# FV-1.net
KiCad netlist of a schematic drawn in Altium Designer
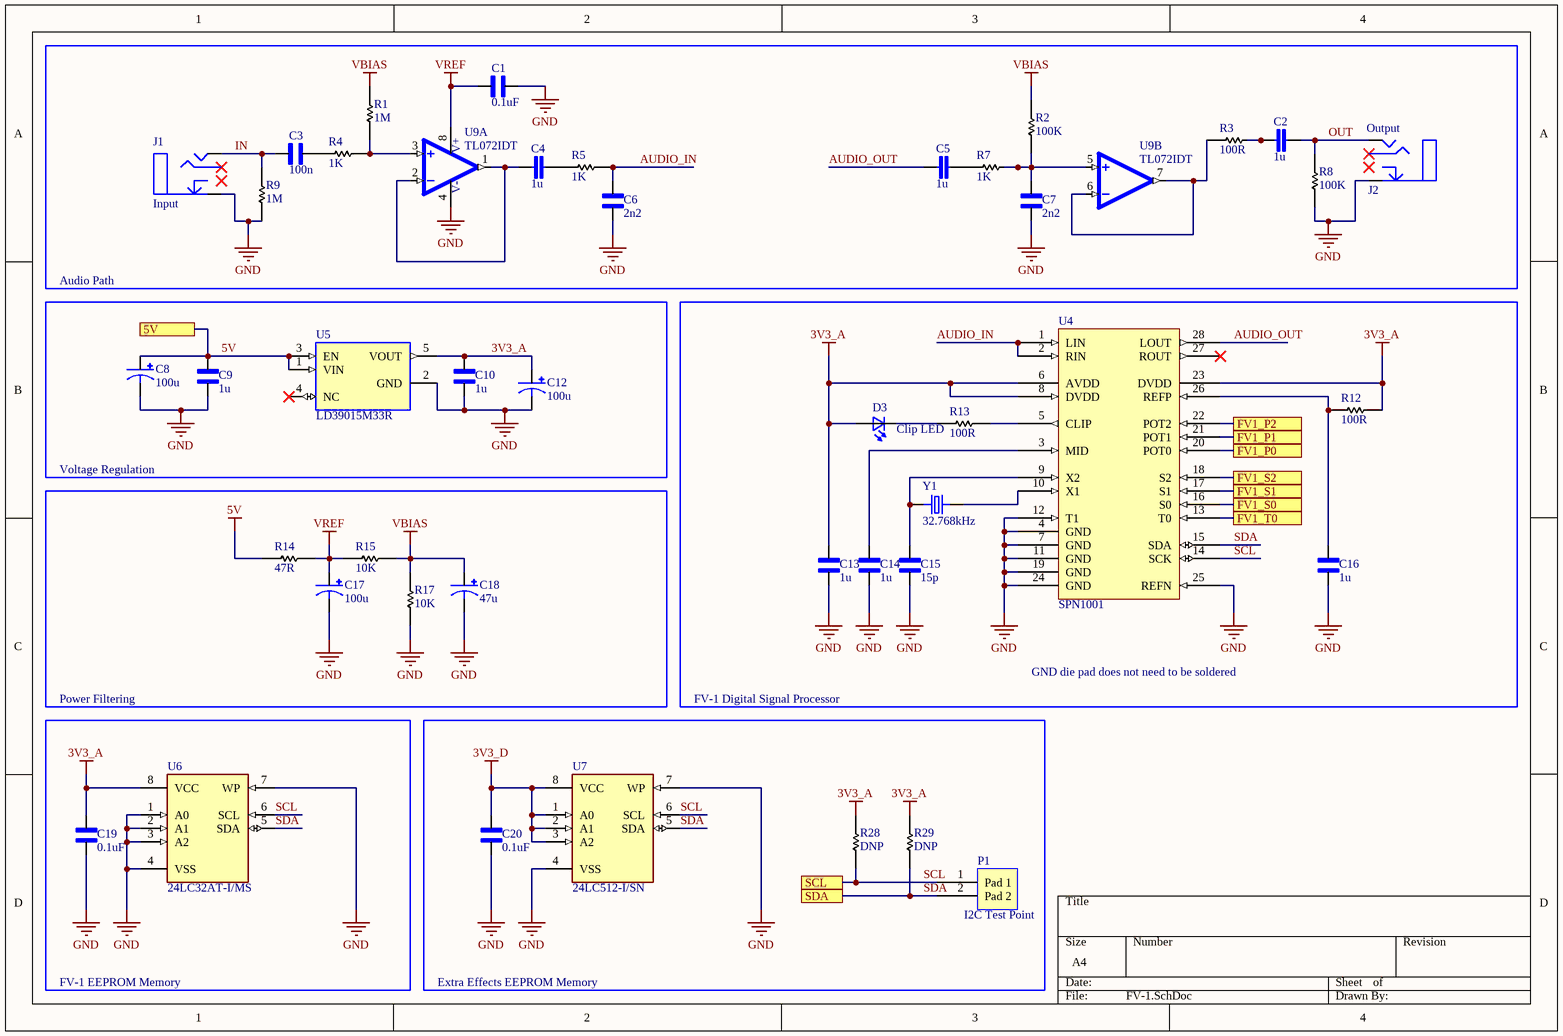
[diagram p0: FV-1.SchDoc]

(export (version "E")
  (design (tool "Eeschema 10.0.6"))
  (components
    (comp (ref "C1")
      (value "0.1uF")
      (footprint "CHIP_0603")
      (description "Generic 0603 Ceramic Capacitor")
      (fields (field (name "MP") "AC0402FR-071ML") (field (name "MF") "Yageo"))
      (libsource (lib "") (part "0603 Ceramic Capacitor_1"))
    )
    (comp (ref "C2")
      (value "1u")
      (footprint "CHIP_1210")
      (description "CAP FILM 1UF 16V 20%")
      (fields
        (field (name "MANUFACTURER") "Panasonic")
        (field (name "MANUFACTURER PART NUMBER") "ECP-U1C105MA5")
      )
      (libsource (lib "Guitar_Multi_Effect_lib") (part "ECP-U1C105MA5"))
    )
    (comp (ref "C3")
      (value "100n")
      (footprint "CAPC3216X180N")
      (description "50V 100nF C0G ±5% 1206 Multilayer Ceramic Capacitors")
      (libsource (lib "Guitar_Multi_Effect_lib") (part "GRM31C5C1H104JA01L"))
    )
    (comp (ref "C4")
      (value "1u")
      (footprint "CHIP_1210")
      (description "CAP FILM 1UF 16V 20%")
      (fields
        (field (name "MANUFACTURER") "Panasonic")
        (field (name "MANUFACTURER PART NUMBER") "ECP-U1C105MA5")
      )
      (libsource (lib "Guitar_Multi_Effect_lib") (part "ECP-U1C105MA5"))
    )
    (comp (ref "C5")
      (value "1u")
      (footprint "CHIP_1210")
      (description "CAP FILM 1UF 16V 20%")
      (fields
        (field (name "MANUFACTURER") "Panasonic")
        (field (name "MANUFACTURER PART NUMBER") "ECP-U1C105MA5")
      )
      (libsource (lib "Guitar_Multi_Effect_lib") (part "ECP-U1C105MA5"))
    )
    (comp (ref "C6")
      (value "2n2")
      (footprint "CHIP_0603")
      (description "2200PF 50V C0G/NP0 0603")
      (libsource (lib "Guitar_Multi_Effect_lib") (part "GRM1885C1H222JA01D"))
    )
    (comp (ref "C7")
      (value "2n2")
      (footprint "CHIP_0603")
      (description "2200PF 50V C0G/NP0 0603")
      (libsource (lib "Guitar_Multi_Effect_lib") (part "GRM1885C1H222JA01D"))
    )
    (comp (ref "C8")
      (value "100u")
      (footprint "UCD1E101MCL1GS")
      (description "CAP ALUM 100UF 25V SMD")
      (libsource (lib "Guitar_Multi_Effect_lib") (part "UCD1E101MCL1GS"))
    )
    (comp (ref "C9")
      (value "1u")
      (footprint "CHIP_0603")
      (description "Generic 0603 Ceramic Capacitor")
      (fields (field (name "MP") "AC0402FR-071ML") (field (name "MF") "Yageo"))
      (libsource (lib "Guitar_Multi_Effect_lib") (part "0603 Ceramic Capacitor"))
    )
    (comp (ref "C10")
      (value "1u")
      (footprint "CHIP_0603")
      (description "Generic 0603 Ceramic Capacitor")
      (fields (field (name "MP") "AC0402FR-071ML") (field (name "MF") "Yageo"))
      (libsource (lib "Guitar_Multi_Effect_lib") (part "0603 Ceramic Capacitor"))
    )
    (comp (ref "C12")
      (value "100u")
      (footprint "UCD1E101MCL1GS")
      (description "CAP ALUM 100UF 25V SMD")
      (libsource (lib "Guitar_Multi_Effect_lib") (part "UCD1E101MCL1GS"))
    )
    (comp (ref "C13")
      (value "1u")
      (footprint "CHIP_0603")
      (description "Generic 0603 Ceramic Capacitor")
      (fields (field (name "MP") "AC0402FR-071ML") (field (name "MF") "Yageo"))
      (libsource (lib "Guitar_Multi_Effect_lib") (part "0603 Ceramic Capacitor"))
    )
    (comp (ref "C14")
      (value "1u")
      (footprint "CHIP_0603")
      (description "Generic 0603 Ceramic Capacitor")
      (fields (field (name "MP") "AC0402FR-071ML") (field (name "MF") "Yageo"))
      (libsource (lib "Guitar_Multi_Effect_lib") (part "0603 Ceramic Capacitor"))
    )
    (comp (ref "C15")
      (value "15p")
      (footprint "CHIP_0603")
      (description "Generic 0603 Ceramic Capacitor")
      (fields (field (name "MP") "AC0402FR-071ML") (field (name "MF") "Yageo"))
      (libsource (lib "Guitar_Multi_Effect_lib") (part "0603 Ceramic Capacitor"))
    )
    (comp (ref "C16")
      (value "1u")
      (footprint "CHIP_0603")
      (description "Generic 0603 Ceramic Capacitor")
      (fields (field (name "MP") "AC0402FR-071ML") (field (name "MF") "Yageo"))
      (libsource (lib "Guitar_Multi_Effect_lib") (part "0603 Ceramic Capacitor"))
    )
    (comp (ref "C17")
      (value "100u")
      (footprint "UCD1E101MCL1GS")
      (description "CAP ALUM 100UF 25V SMD")
      (libsource (lib "Guitar_Multi_Effect_lib") (part "UCD1E101MCL1GS"))
    )
    (comp (ref "C18")
      (value "47u")
      (footprint "EEE1EA470WAP")
      (description "CAP ALUM 47UF 25V SMD")
      (libsource (lib "Guitar_Multi_Effect_lib") (part "EEE1EA470WAP"))
    )
    (comp (ref "C19")
      (value "0.1uF")
      (footprint "CHIP_0603")
      (description "Generic 0603 Ceramic Capacitor")
      (fields (field (name "MP") "AC0402FR-071ML") (field (name "MF") "Yageo"))
      (libsource (lib "Guitar_Multi_Effect_lib") (part "0603 Ceramic Capacitor"))
    )
    (comp (ref "C20")
      (value "0.1uF")
      (footprint "CHIP_0603")
      (description "Generic 0603 Ceramic Capacitor")
      (fields (field (name "MP") "AC0402FR-071ML") (field (name "MF") "Yageo"))
      (libsource (lib "Guitar_Multi_Effect_lib") (part "0603 Ceramic Capacitor"))
    )
    (comp (ref "D3")
      (value "Clip LED")
      (footprint "0603 LED Generic")
      (description "0603 Generic LED")
      (libsource (lib "Guitar_Multi_Effect_lib") (part "0603 Generic LED"))
    )
    (comp (ref "J1")
      (value "Input")
      (footprint "2 Test Points")
      (description "Sodler pads for audio jacks")
      (libsource (lib "Guitar_Multi_Effect_lib") (part "Audio_Solder_Pads"))
    )
    (comp (ref "J2")
      (value "Output")
      (footprint "2 Test Points")
      (description "Sodler pads for audio jacks")
      (libsource (lib "Guitar_Multi_Effect_lib") (part "Audio_Solder_Pads"))
    )
    (comp (ref "P1")
      (value "I2C Test Point")
      (footprint "2 Test Points")
      (libsource (lib "Guitar_Multi_Effect_lib") (part "Double Test Point"))
    )
    (comp (ref "R1")
      (value "1M")
      (footprint "CHIP_R_0603")
      (description "Generic 0603 Resistor")
      (libsource (lib "Guitar_Multi_Effect_lib") (part "0603 Generic Resistor"))
    )
    (comp (ref "R2")
      (value "100K")
      (footprint "CHIP_R_0603")
      (description "Generic 0603 Resistor")
      (libsource (lib "Guitar_Multi_Effect_lib") (part "0603 Generic Resistor"))
    )
    (comp (ref "R3")
      (value "100R")
      (footprint "CHIP_R_0603")
      (description "Generic 0603 Resistor")
      (libsource (lib "Guitar_Multi_Effect_lib") (part "0603 Generic Resistor"))
    )
    (comp (ref "R4")
      (value "1K")
      (footprint "CHIP_R_0603")
      (description "Generic 0603 Resistor")
      (libsource (lib "Guitar_Multi_Effect_lib") (part "0603 Generic Resistor"))
    )
    (comp (ref "R5")
      (value "1K")
      (footprint "CHIP_R_0603")
      (description "Generic 0603 Resistor")
      (libsource (lib "Guitar_Multi_Effect_lib") (part "0603 Generic Resistor"))
    )
    (comp (ref "R7")
      (value "1K")
      (footprint "CHIP_R_0603")
      (description "Generic 0603 Resistor")
      (libsource (lib "Guitar_Multi_Effect_lib") (part "0603 Generic Resistor"))
    )
    (comp (ref "R8")
      (value "100K")
      (footprint "CHIP_R_0603")
      (description "Generic 0603 Resistor")
      (libsource (lib "Guitar_Multi_Effect_lib") (part "0603 Generic Resistor"))
    )
    (comp (ref "R9")
      (value "1M")
      (footprint "CHIP_R_0603")
      (description "Generic 0603 Resistor")
      (libsource (lib "Guitar_Multi_Effect_lib") (part "0603 Generic Resistor"))
    )
    (comp (ref "R12")
      (value "100R")
      (footprint "CHIP_R_0603")
      (description "Generic 0603 Resistor")
      (libsource (lib "Guitar_Multi_Effect_lib") (part "0603 Generic Resistor"))
    )
    (comp (ref "R13")
      (value "100R")
      (footprint "CHIP_R_0603")
      (description "Generic 0603 Resistor")
      (libsource (lib "Guitar_Multi_Effect_lib") (part "0603 Generic Resistor"))
    )
    (comp (ref "R14")
      (value "47R")
      (footprint "CHIP_R_0603")
      (description "Generic 0603 Resistor")
      (libsource (lib "Guitar_Multi_Effect_lib") (part "0603 Generic Resistor"))
    )
    (comp (ref "R15")
      (value "10K")
      (footprint "CHIP_R_0603")
      (description "Generic 0603 Resistor")
      (libsource (lib "Guitar_Multi_Effect_lib") (part "0603 Generic Resistor"))
    )
    (comp (ref "R17")
      (value "10K")
      (footprint "CHIP_R_0603")
      (description "Generic 0603 Resistor")
      (libsource (lib "Guitar_Multi_Effect_lib") (part "0603 Generic Resistor"))
    )
    (comp (ref "R28")
      (value "DNP")
      (footprint "CHIP_R_0603")
      (description "Generic 0603 Resistor")
      (libsource (lib "Guitar_Multi_Effect_lib") (part "0603 Generic Resistor"))
    )
    (comp (ref "R29")
      (value "DNP")
      (footprint "CHIP_R_0603")
      (description "Generic 0603 Resistor")
      (libsource (lib "Guitar_Multi_Effect_lib") (part "0603 Generic Resistor"))
    )
    (comp (ref "U4")
      (value "SPN1001")
      (footprint "SOIC-28")
      (libsource (lib "Guitar_Multi_Effect_lib") (part "SPN1001"))
    )
    (comp (ref "U5")
      (value "LD39015M33R")
      (footprint "SOT-23")
      (description "Fixed 3.3V LDO 150mA SOT-23-5 Linear Voltage Regulator")
      (libsource (lib "Guitar_Multi_Effect_lib") (part "LD39015M33R"))
    )
    (comp (ref "U6")
      (value "24LC32AT-I/MS")
      (footprint "24LC32AT-I/MS")
      (description "32K I2C Serial EEPROM")
      (libsource (lib "Guitar_Multi_Effect_lib") (part "24LC32AT-I/MS"))
    )
    (comp (ref "U7")
      (value "24LC512-I/SN")
      (footprint "24LC512-I/SN")
      (description "512K I2C Serial EEPROM")
      (libsource (lib "Guitar_Multi_Effect_lib") (part "24LC512-I/SN"))
    )
    (comp (ref "U9")
      (value "TL072IDT")
      (footprint "TL072BIDT")
      (description "J-FET Amplifier 2 Circuit 8-SO")
      (fields (field (name "MF") "STMicroelectronics"))
      (libsource (lib "Guitar_Multi_Effect_lib") (part "TL072IDT"))
    )
    (comp (ref "Y1")
      (value "32.768kHz")
      (footprint "XTAL_ABS07-32.768KHZ-T")
      (description "32.768kHz Â±20ppm Crystal 12.5pF 70 kOhms 2-SMD, No Lead")
      (fields (field (name "MF") "Abracon LLC") (field (name "MP") "ABS07-32.768KHZ"))
      (libsource (lib "Guitar_Multi_Effect_lib") (part "ABS07-32.768KHZ-T"))
    )
  )
  (nets
    (net (code "1") (name "/AUDIO_IN") (class "Default")
      (node (ref "C6") (pin "1") (pinfunction "1_1") (pintype "passive"))
      (node (ref "R5") (pin "2") (pinfunction "2_2") (pintype "passive"))
      (node (ref "U4") (pin "1") (pinfunction "LIN_1") (pintype "input"))
      (node (ref "U4") (pin "2") (pinfunction "RIN_2") (pintype "input"))
    )
    (net (code "2") (name "/AUDIO_OUT") (class "Default")
      (node (ref "C5") (pin "2") (pinfunction "2_2") (pintype "passive"))
      (node (ref "U4") (pin "28") (pinfunction "LOUT_28") (pintype "output"))
    )
    (net (code "3") (name "/FV1_P0") (class "Default")
      (node (ref "U4") (pin "20") (pinfunction "POT0_20") (pintype "input"))
    )
    (net (code "4") (name "/FV1_P1") (class "Default")
      (node (ref "U4") (pin "21") (pinfunction "POT1_21") (pintype "input"))
    )
    (net (code "5") (name "/FV1_P2") (class "Default")
      (node (ref "U4") (pin "22") (pinfunction "POT2_22") (pintype "input"))
    )
    (net (code "6") (name "/FV1_S0") (class "Default")
      (node (ref "U4") (pin "16") (pinfunction "S0_16") (pintype "input"))
    )
    (net (code "7") (name "/FV1_S1") (class "Default")
      (node (ref "U4") (pin "17") (pinfunction "S1_17") (pintype "input"))
    )
    (net (code "8") (name "/FV1_S2") (class "Default")
      (node (ref "U4") (pin "18") (pinfunction "S2_18") (pintype "input"))
    )
    (net (code "9") (name "/FV1_T0") (class "Default")
      (node (ref "U4") (pin "13") (pinfunction "T0_13") (pintype "input"))
    )
    (net (code "10") (name "/IN") (class "Default")
      (node (ref "C3") (pin "2") (pinfunction "2_2") (pintype "passive"))
      (node (ref "J1") (pin "1") (pinfunction "1_1") (pintype "passive"))
      (node (ref "R9") (pin "1") (pinfunction "1_1") (pintype "passive"))
    )
    (net (code "11") (name "/OUT") (class "Default")
      (node (ref "C2") (pin "1") (pinfunction "1_1") (pintype "passive"))
      (node (ref "J2") (pin "1") (pinfunction "1_1") (pintype "passive"))
      (node (ref "R8") (pin "1") (pinfunction "1_1") (pintype "passive"))
    )
    (net (code "12") (name "/SCL") (class "Default")
      (node (ref "P1") (pin "1") (pinfunction "Pad_1_1") (pintype "passive"))
      (node (ref "R28") (pin "2") (pinfunction "2_2") (pintype "passive"))
      (node (ref "U4") (pin "14") (pinfunction "SCK_14") (pintype "bidirectional"))
      (node (ref "U6") (pin "6") (pinfunction "SCL_6") (pintype "input"))
      (node (ref "U7") (pin "6") (pinfunction "SCL_6") (pintype "input"))
    )
    (net (code "13") (name "/SDA") (class "Default")
      (node (ref "P1") (pin "2") (pinfunction "Pad_2_2") (pintype "passive"))
      (node (ref "R29") (pin "2") (pinfunction "2_2") (pintype "passive"))
      (node (ref "U4") (pin "15") (pinfunction "SDA_15") (pintype "bidirectional"))
      (node (ref "U6") (pin "5") (pinfunction "SDA_5") (pintype "bidirectional"))
      (node (ref "U7") (pin "5") (pinfunction "SDA_5") (pintype "bidirectional"))
    )
    (net (code "14") (name "3V3_A") (class "Default")
      (node (ref "C10") (pin "1") (pinfunction "1_1") (pintype "passive"))
      (node (ref "C12") (pin "+") (pinfunction "+_+") (pintype "passive"))
      (node (ref "C13") (pin "1") (pinfunction "1_1") (pintype "passive"))
      (node (ref "C19") (pin "1") (pinfunction "1_1") (pintype "passive"))
      (node (ref "D3") (pin "2") (pinfunction "A2_2") (pintype "passive"))
      (node (ref "R12") (pin "2") (pinfunction "2_2") (pintype "passive"))
      (node (ref "R28") (pin "1") (pinfunction "1_1") (pintype "passive"))
      (node (ref "R29") (pin "1") (pinfunction "1_1") (pintype "passive"))
      (node (ref "U4") (pin "23") (pinfunction "DVDD_23") (pintype "power_in"))
      (node (ref "U4") (pin "6") (pinfunction "AVDD_6") (pintype "power_in"))
      (node (ref "U4") (pin "8") (pinfunction "DVDD_8") (pintype "input"))
      (node (ref "U5") (pin "5") (pinfunction "VOUT_5") (pintype "output"))
      (node (ref "U6") (pin "8") (pinfunction "VCC_8") (pintype "power_in"))
    )
    (net (code "15") (name "3V3_D") (class "Default")
      (node (ref "C20") (pin "1") (pinfunction "1_1") (pintype "passive"))
      (node (ref "U7") (pin "1") (pinfunction "A0_1") (pintype "input"))
      (node (ref "U7") (pin "2") (pinfunction "A1_2") (pintype "input"))
      (node (ref "U7") (pin "3") (pinfunction "A2_3") (pintype "input"))
      (node (ref "U7") (pin "8") (pinfunction "VCC_8") (pintype "power_in"))
    )
    (net (code "16") (name "5V") (class "Default")
      (node (ref "C8") (pin "+") (pinfunction "+_+") (pintype "passive"))
      (node (ref "C9") (pin "1") (pinfunction "1_1") (pintype "passive"))
      (node (ref "R14") (pin "2") (pinfunction "2_2") (pintype "passive"))
      (node (ref "U5") (pin "1") (pinfunction "VIN_1") (pintype "input"))
      (node (ref "U5") (pin "3") (pinfunction "EN_3") (pintype "input"))
    )
    (net (code "17") (name "GND") (class "Default")
      (node (ref "C1") (pin "2") (pinfunction "2_2") (pintype "passive"))
      (node (ref "C10") (pin "2") (pinfunction "2_2") (pintype "passive"))
      (node (ref "C12") (pin "-") (pinfunction "-_-") (pintype "passive"))
      (node (ref "C13") (pin "2") (pinfunction "2_2") (pintype "passive"))
      (node (ref "C14") (pin "2") (pinfunction "2_2") (pintype "passive"))
      (node (ref "C15") (pin "2") (pinfunction "2_2") (pintype "passive"))
      (node (ref "C16") (pin "2") (pinfunction "2_2") (pintype "passive"))
      (node (ref "C17") (pin "-") (pinfunction "-_-") (pintype "passive"))
      (node (ref "C18") (pin "-") (pinfunction "-_-") (pintype "passive"))
      (node (ref "C19") (pin "2") (pinfunction "2_2") (pintype "passive"))
      (node (ref "C20") (pin "2") (pinfunction "2_2") (pintype "passive"))
      (node (ref "C6") (pin "2") (pinfunction "2_2") (pintype "passive"))
      (node (ref "C7") (pin "2") (pinfunction "2_2") (pintype "passive"))
      (node (ref "C8") (pin "-") (pinfunction "-_-") (pintype "passive"))
      (node (ref "C9") (pin "2") (pinfunction "2_2") (pintype "passive"))
      (node (ref "J1") (pin "2") (pinfunction "2_2") (pintype "passive"))
      (node (ref "J2") (pin "2") (pinfunction "2_2") (pintype "passive"))
      (node (ref "R17") (pin "2") (pinfunction "2_2") (pintype "passive"))
      (node (ref "R8") (pin "2") (pinfunction "2_2") (pintype "passive"))
      (node (ref "R9") (pin "2") (pinfunction "2_2") (pintype "passive"))
      (node (ref "U4") (pin "11") (pinfunction "GND_11") (pintype "power_in"))
      (node (ref "U4") (pin "12") (pinfunction "T1_12") (pintype "input"))
      (node (ref "U4") (pin "19") (pinfunction "GND_19") (pintype "power_in"))
      (node (ref "U4") (pin "24") (pinfunction "GND_24") (pintype "power_in"))
      (node (ref "U4") (pin "25") (pinfunction "REFN_25") (pintype "input"))
      (node (ref "U4") (pin "4") (pinfunction "GND_4") (pintype "power_in"))
      (node (ref "U4") (pin "7") (pinfunction "GND_7") (pintype "power_in"))
      (node (ref "U5") (pin "2") (pinfunction "GND_2") (pintype "power_in"))
      (node (ref "U6") (pin "1") (pinfunction "A0_1") (pintype "input"))
      (node (ref "U6") (pin "2") (pinfunction "A1_2") (pintype "input"))
      (node (ref "U6") (pin "3") (pinfunction "A2_3") (pintype "input"))
      (node (ref "U6") (pin "4") (pinfunction "VSS_4") (pintype "passive"))
      (node (ref "U6") (pin "7") (pinfunction "WP_7") (pintype "input"))
      (node (ref "U7") (pin "4") (pinfunction "VSS_4") (pintype "passive"))
      (node (ref "U7") (pin "7") (pinfunction "WP_7") (pintype "input"))
      (node (ref "U9") (pin "4") (pinfunction "V-_4") (pintype "power_in"))
    )
    (net (code "18") (name "Net-(C2-Pad2)") (class "Default")
      (node (ref "C2") (pin "2") (pinfunction "2_2") (pintype "passive"))
      (node (ref "R3") (pin "2") (pinfunction "2_2") (pintype "passive"))
    )
    (net (code "19") (name "Net-(C3-Pad1)") (class "Default")
      (node (ref "C3") (pin "1") (pinfunction "1_1") (pintype "passive"))
      (node (ref "R4") (pin "1") (pinfunction "1_1") (pintype "passive"))
    )
    (net (code "20") (name "Net-(C4-Pad1)") (class "Default")
      (node (ref "C4") (pin "1") (pinfunction "1_1") (pintype "passive"))
      (node (ref "R5") (pin "1") (pinfunction "1_1") (pintype "passive"))
    )
    (net (code "21") (name "Net-(C5-Pad1)") (class "Default")
      (node (ref "C5") (pin "1") (pinfunction "1_1") (pintype "passive"))
      (node (ref "R7") (pin "1") (pinfunction "1_1") (pintype "passive"))
    )
    (net (code "22") (name "Net-(D3-K2)") (class "Default")
      (node (ref "D3") (pin "1") (pinfunction "K2_1") (pintype "passive"))
      (node (ref "R13") (pin "1") (pinfunction "1_1") (pintype "passive"))
    )
    (net (code "23") (name "Net-(U4-CLIP)") (class "Default")
      (node (ref "R13") (pin "2") (pinfunction "2_2") (pintype "passive"))
      (node (ref "U4") (pin "5") (pinfunction "CLIP_5") (pintype "output"))
    )
    (net (code "24") (name "Net-(U4-MID)") (class "Default")
      (node (ref "C14") (pin "1") (pinfunction "1_1") (pintype "passive"))
      (node (ref "U4") (pin "3") (pinfunction "MID_3") (pintype "input"))
    )
    (net (code "25") (name "Net-(U4-REFP)") (class "Default")
      (node (ref "C16") (pin "1") (pinfunction "1_1") (pintype "passive"))
      (node (ref "R12") (pin "1") (pinfunction "1_1") (pintype "passive"))
      (node (ref "U4") (pin "26") (pinfunction "REFP_26") (pintype "input"))
    )
    (net (code "26") (name "Net-(U4-X1)") (class "Default")
      (node (ref "U4") (pin "10") (pinfunction "X1_10") (pintype "input"))
      (node (ref "Y1") (pin "1") (pinfunction "1_1") (pintype "passive"))
    )
    (net (code "27") (name "Net-(U4-X2)") (class "Default")
      (node (ref "C15") (pin "1") (pinfunction "1_1") (pintype "passive"))
      (node (ref "U4") (pin "9") (pinfunction "X2_9") (pintype "input"))
      (node (ref "Y1") (pin "2") (pinfunction "2_2") (pintype "passive"))
    )
    (net (code "28") (name "Net-(U9A-+IN1)") (class "Default")
      (node (ref "R1") (pin "2") (pinfunction "2_2") (pintype "passive"))
      (node (ref "R4") (pin "2") (pinfunction "2_2") (pintype "passive"))
      (node (ref "U9") (pin "3") (pinfunction "+IN1_3") (pintype "input"))
    )
    (net (code "29") (name "Net-(U9A--IN1)") (class "Default")
      (node (ref "C4") (pin "2") (pinfunction "2_2") (pintype "passive"))
      (node (ref "U9") (pin "1") (pinfunction "OUT1_1") (pintype "output"))
      (node (ref "U9") (pin "2") (pinfunction "-IN1_2") (pintype "input"))
    )
    (net (code "30") (name "Net-(U9B-+IN2)") (class "Default")
      (node (ref "C7") (pin "1") (pinfunction "1_1") (pintype "passive"))
      (node (ref "R2") (pin "2") (pinfunction "2_2") (pintype "passive"))
      (node (ref "R7") (pin "2") (pinfunction "2_2") (pintype "passive"))
      (node (ref "U9") (pin "5") (pinfunction "+IN2_5") (pintype "input"))
    )
    (net (code "31") (name "Net-(U9B--IN2)") (class "Default")
      (node (ref "R3") (pin "1") (pinfunction "1_1") (pintype "passive"))
      (node (ref "U9") (pin "6") (pinfunction "-IN2_6") (pintype "input"))
      (node (ref "U9") (pin "7") (pinfunction "OUT2_7") (pintype "output"))
    )
    (net (code "32") (name "VBIAS") (class "Default")
      (node (ref "C18") (pin "+") (pinfunction "+_+") (pintype "passive"))
      (node (ref "R1") (pin "1") (pinfunction "1_1") (pintype "passive"))
      (node (ref "R15") (pin "1") (pinfunction "1_1") (pintype "passive"))
      (node (ref "R17") (pin "1") (pinfunction "1_1") (pintype "passive"))
      (node (ref "R2") (pin "1") (pinfunction "1_1") (pintype "passive"))
    )
    (net (code "33") (name "VREF") (class "Default")
      (node (ref "C1") (pin "1") (pinfunction "1_1") (pintype "passive"))
      (node (ref "C17") (pin "+") (pinfunction "+_+") (pintype "passive"))
      (node (ref "R14") (pin "1") (pinfunction "1_1") (pintype "passive"))
      (node (ref "R15") (pin "2") (pinfunction "2_2") (pintype "passive"))
      (node (ref "U9") (pin "8") (pinfunction "V+_8") (pintype "power_in"))
    )
    (net (code "34") (name "unconnected-(U4-ROUT-Pad27)") (class "Default")
      (node (ref "U4") (pin "27") (pinfunction "ROUT_27") (pintype "output+no_connect"))
    )
    (net (code "35") (name "unconnected-(U5-NC-Pad4)") (class "Default")
      (node (ref "U5") (pin "4") (pinfunction "NC_4") (pintype "bidirectional+no_connect"))
    )
  )
)
